# lcd22.net
KiCad netlist of a schematic drawn in EAGLE
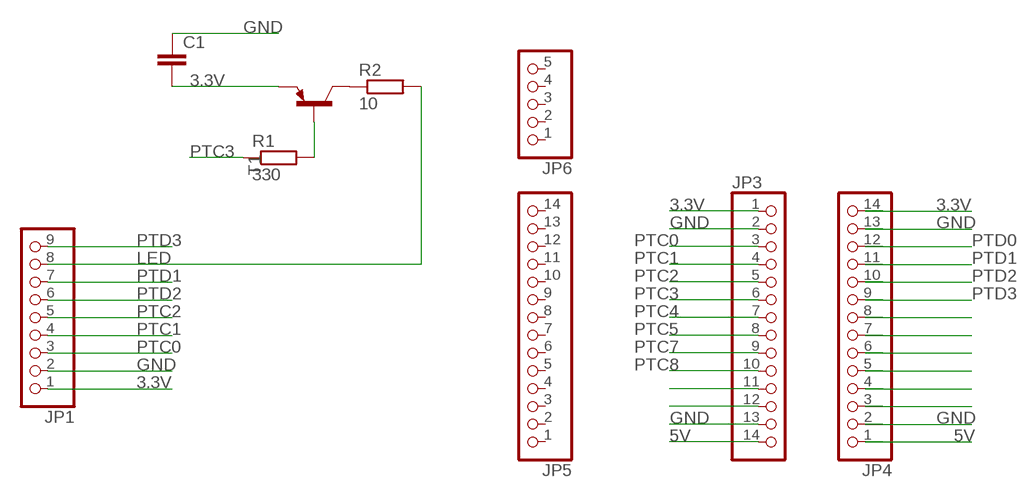
[diagram p0: schematic, sheet 1]

(export (version "E")
  (design (tool "Eeschema 10.0.6"))
  (components
    (comp (ref "C1")
      (value "C-EU025-025X050")
      (footprint "eagle-import:C025-025X050")
      (libsource (lib "eagle-import") (part "C-EU025-025X050"))
    )
    (comp (ref "JP1")
      (value "PINHD-1X9")
      (footprint "eagle-import:1X09")
      (libsource (lib "eagle-import") (part "PINHD-1X9"))
    )
    (comp (ref "JP3")
      (value "PINHD-1X14")
      (footprint "eagle-import:1X14")
      (libsource (lib "eagle-import") (part "PINHD-1X14"))
    )
    (comp (ref "JP4")
      (value "PINHD-1X14")
      (footprint "eagle-import:1X14")
      (libsource (lib "eagle-import") (part "PINHD-1X14"))
    )
    (comp (ref "JP5")
      (value "PINHD-1X14")
      (footprint "eagle-import:1X14")
      (libsource (lib "eagle-import") (part "PINHD-1X14"))
    )
    (comp (ref "JP6")
      (value "PINHD-1X5")
      (footprint "eagle-import:1X05")
      (libsource (lib "eagle-import") (part "PINHD-1X5"))
    )
    (comp (ref "R1")
      (value "330")
      (footprint "eagle-import:0207_10")
      (libsource (lib "eagle-import") (part "R-EU_0207/10"))
    )
    (comp (ref "R2")
      (value "10")
      (footprint "eagle-import:0207_10")
      (libsource (lib "eagle-import") (part "R-EU_0207/10"))
    )
    (comp (ref "T1")
      (value "BC557C-PNP-TO92-EBC")
      (footprint "eagle-import:TO92-EBC")
      (libsource (lib "eagle-import") (part "-PNP-TO92-EBCBC557C"))
    )
  )
  (nets
    (net (code "1") (name "/3.3V") (class "Default")
      (node (ref "C1") (pin "2") (pinfunction "2_2") (pintype "passive"))
      (node (ref "JP1") (pin "1") (pinfunction "1_1") (pintype "passive"))
      (node (ref "JP3") (pin "1") (pinfunction "1_1") (pintype "passive"))
      (node (ref "JP4") (pin "14") (pinfunction "14_14") (pintype "passive"))
      (node (ref "T1") (pin "E") (pinfunction "E_E") (pintype "passive"))
    )
    (net (code "2") (name "/5V") (class "Default")
      (node (ref "JP3") (pin "14") (pinfunction "14_14") (pintype "passive"))
      (node (ref "JP4") (pin "1") (pinfunction "1_1") (pintype "passive"))
    )
    (net (code "3") (name "/GND") (class "Default")
      (node (ref "C1") (pin "1") (pinfunction "1_1") (pintype "passive"))
      (node (ref "JP1") (pin "2") (pinfunction "2_2") (pintype "passive"))
      (node (ref "JP3") (pin "13") (pinfunction "13_13") (pintype "passive"))
      (node (ref "JP3") (pin "2") (pinfunction "2_2") (pintype "passive"))
      (node (ref "JP4") (pin "13") (pinfunction "13_13") (pintype "passive"))
      (node (ref "JP4") (pin "2") (pinfunction "2_2") (pintype "passive"))
    )
    (net (code "4") (name "/LED") (class "Default")
      (node (ref "JP1") (pin "8") (pinfunction "8_8") (pintype "passive"))
      (node (ref "R2") (pin "2") (pinfunction "2_2") (pintype "passive"))
    )
    (net (code "5") (name "/PTC0") (class "Default")
      (node (ref "JP1") (pin "3") (pinfunction "3_3") (pintype "passive"))
      (node (ref "JP3") (pin "3") (pinfunction "3_3") (pintype "passive"))
    )
    (net (code "6") (name "/PTC1") (class "Default")
      (node (ref "JP1") (pin "4") (pinfunction "4_4") (pintype "passive"))
      (node (ref "JP3") (pin "4") (pinfunction "4_4") (pintype "passive"))
    )
    (net (code "7") (name "/PTC2") (class "Default")
      (node (ref "JP1") (pin "5") (pinfunction "5_5") (pintype "passive"))
      (node (ref "JP3") (pin "5") (pinfunction "5_5") (pintype "passive"))
    )
    (net (code "8") (name "/PTC3") (class "Default")
      (node (ref "JP3") (pin "6") (pinfunction "6_6") (pintype "passive"))
      (node (ref "R1") (pin "1") (pinfunction "1_1") (pintype "passive"))
    )
    (net (code "9") (name "/PTC4") (class "Default")
      (node (ref "JP3") (pin "7") (pinfunction "7_7") (pintype "passive"))
    )
    (net (code "10") (name "/PTC5") (class "Default")
      (node (ref "JP3") (pin "8") (pinfunction "8_8") (pintype "passive"))
    )
    (net (code "11") (name "/PTC7") (class "Default")
      (node (ref "JP3") (pin "9") (pinfunction "9_9") (pintype "passive"))
    )
    (net (code "12") (name "/PTC8") (class "Default")
      (node (ref "JP3") (pin "10") (pinfunction "10_10") (pintype "passive"))
    )
    (net (code "13") (name "/PTD0") (class "Default")
      (node (ref "JP4") (pin "12") (pinfunction "12_12") (pintype "passive"))
    )
    (net (code "14") (name "/PTD1") (class "Default")
      (node (ref "JP1") (pin "7") (pinfunction "7_7") (pintype "passive"))
      (node (ref "JP4") (pin "11") (pinfunction "11_11") (pintype "passive"))
    )
    (net (code "15") (name "/PTD2") (class "Default")
      (node (ref "JP1") (pin "6") (pinfunction "6_6") (pintype "passive"))
      (node (ref "JP4") (pin "10") (pinfunction "10_10") (pintype "passive"))
    )
    (net (code "16") (name "/PTD3") (class "Default")
      (node (ref "JP1") (pin "9") (pinfunction "9_9") (pintype "passive"))
      (node (ref "JP4") (pin "9") (pinfunction "9_9") (pintype "passive"))
    )
    (net (code "17") (name "Net-(R1-Pad2)") (class "Default")
      (node (ref "R1") (pin "2") (pinfunction "2_2") (pintype "passive"))
      (node (ref "T1") (pin "B") (pinfunction "B_B") (pintype "passive"))
    )
    (net (code "18") (name "Net-(R2-Pad1)") (class "Default")
      (node (ref "R2") (pin "1") (pinfunction "1_1") (pintype "passive"))
      (node (ref "T1") (pin "C") (pinfunction "C_C") (pintype "passive"))
    )
    (net (code "19") (name "unconnected-(JP3-Pad11)") (class "Default")
      (node (ref "JP3") (pin "11") (pinfunction "11_11") (pintype "passive"))
    )
    (net (code "20") (name "unconnected-(JP3-Pad12)") (class "Default")
      (node (ref "JP3") (pin "12") (pinfunction "12_12") (pintype "passive"))
    )
    (net (code "21") (name "unconnected-(JP4-Pad3)") (class "Default")
      (node (ref "JP4") (pin "3") (pinfunction "3_3") (pintype "passive"))
    )
    (net (code "22") (name "unconnected-(JP4-Pad4)") (class "Default")
      (node (ref "JP4") (pin "4") (pinfunction "4_4") (pintype "passive"))
    )
    (net (code "23") (name "unconnected-(JP4-Pad5)") (class "Default")
      (node (ref "JP4") (pin "5") (pinfunction "5_5") (pintype "passive"))
    )
    (net (code "24") (name "unconnected-(JP4-Pad6)") (class "Default")
      (node (ref "JP4") (pin "6") (pinfunction "6_6") (pintype "passive"))
    )
    (net (code "25") (name "unconnected-(JP4-Pad7)") (class "Default")
      (node (ref "JP4") (pin "7") (pinfunction "7_7") (pintype "passive"))
    )
    (net (code "26") (name "unconnected-(JP4-Pad8)") (class "Default")
      (node (ref "JP4") (pin "8") (pinfunction "8_8") (pintype "passive"))
    )
    (net (code "27") (name "unconnected-(JP5-Pad1)") (class "Default")
      (node (ref "JP5") (pin "1") (pinfunction "1_1") (pintype "passive"))
    )
    (net (code "28") (name "unconnected-(JP5-Pad2)") (class "Default")
      (node (ref "JP5") (pin "2") (pinfunction "2_2") (pintype "passive"))
    )
    (net (code "29") (name "unconnected-(JP5-Pad3)") (class "Default")
      (node (ref "JP5") (pin "3") (pinfunction "3_3") (pintype "passive"))
    )
    (net (code "30") (name "unconnected-(JP5-Pad4)") (class "Default")
      (node (ref "JP5") (pin "4") (pinfunction "4_4") (pintype "passive"))
    )
    (net (code "31") (name "unconnected-(JP5-Pad5)") (class "Default")
      (node (ref "JP5") (pin "5") (pinfunction "5_5") (pintype "passive"))
    )
    (net (code "32") (name "unconnected-(JP5-Pad6)") (class "Default")
      (node (ref "JP5") (pin "6") (pinfunction "6_6") (pintype "passive"))
    )
    (net (code "33") (name "unconnected-(JP5-Pad7)") (class "Default")
      (node (ref "JP5") (pin "7") (pinfunction "7_7") (pintype "passive"))
    )
    (net (code "34") (name "unconnected-(JP5-Pad8)") (class "Default")
      (node (ref "JP5") (pin "8") (pinfunction "8_8") (pintype "passive"))
    )
    (net (code "35") (name "unconnected-(JP5-Pad9)") (class "Default")
      (node (ref "JP5") (pin "9") (pinfunction "9_9") (pintype "passive"))
    )
    (net (code "36") (name "unconnected-(JP5-Pad10)") (class "Default")
      (node (ref "JP5") (pin "10") (pinfunction "10_10") (pintype "passive"))
    )
    (net (code "37") (name "unconnected-(JP5-Pad11)") (class "Default")
      (node (ref "JP5") (pin "11") (pinfunction "11_11") (pintype "passive"))
    )
    (net (code "38") (name "unconnected-(JP5-Pad12)") (class "Default")
      (node (ref "JP5") (pin "12") (pinfunction "12_12") (pintype "passive"))
    )
    (net (code "39") (name "unconnected-(JP5-Pad13)") (class "Default")
      (node (ref "JP5") (pin "13") (pinfunction "13_13") (pintype "passive"))
    )
    (net (code "40") (name "unconnected-(JP5-Pad14)") (class "Default")
      (node (ref "JP5") (pin "14") (pinfunction "14_14") (pintype "passive"))
    )
    (net (code "41") (name "unconnected-(JP6-Pad1)") (class "Default")
      (node (ref "JP6") (pin "1") (pinfunction "1_1") (pintype "passive"))
    )
    (net (code "42") (name "unconnected-(JP6-Pad2)") (class "Default")
      (node (ref "JP6") (pin "2") (pinfunction "2_2") (pintype "passive"))
    )
    (net (code "43") (name "unconnected-(JP6-Pad3)") (class "Default")
      (node (ref "JP6") (pin "3") (pinfunction "3_3") (pintype "passive"))
    )
    (net (code "44") (name "unconnected-(JP6-Pad4)") (class "Default")
      (node (ref "JP6") (pin "4") (pinfunction "4_4") (pintype "passive"))
    )
    (net (code "45") (name "unconnected-(JP6-Pad5)") (class "Default")
      (node (ref "JP6") (pin "5") (pinfunction "5_5") (pintype "passive"))
    )
  )
)
